# Pump_Agri.net
KiCad netlist of a schematic drawn in Altium Designer
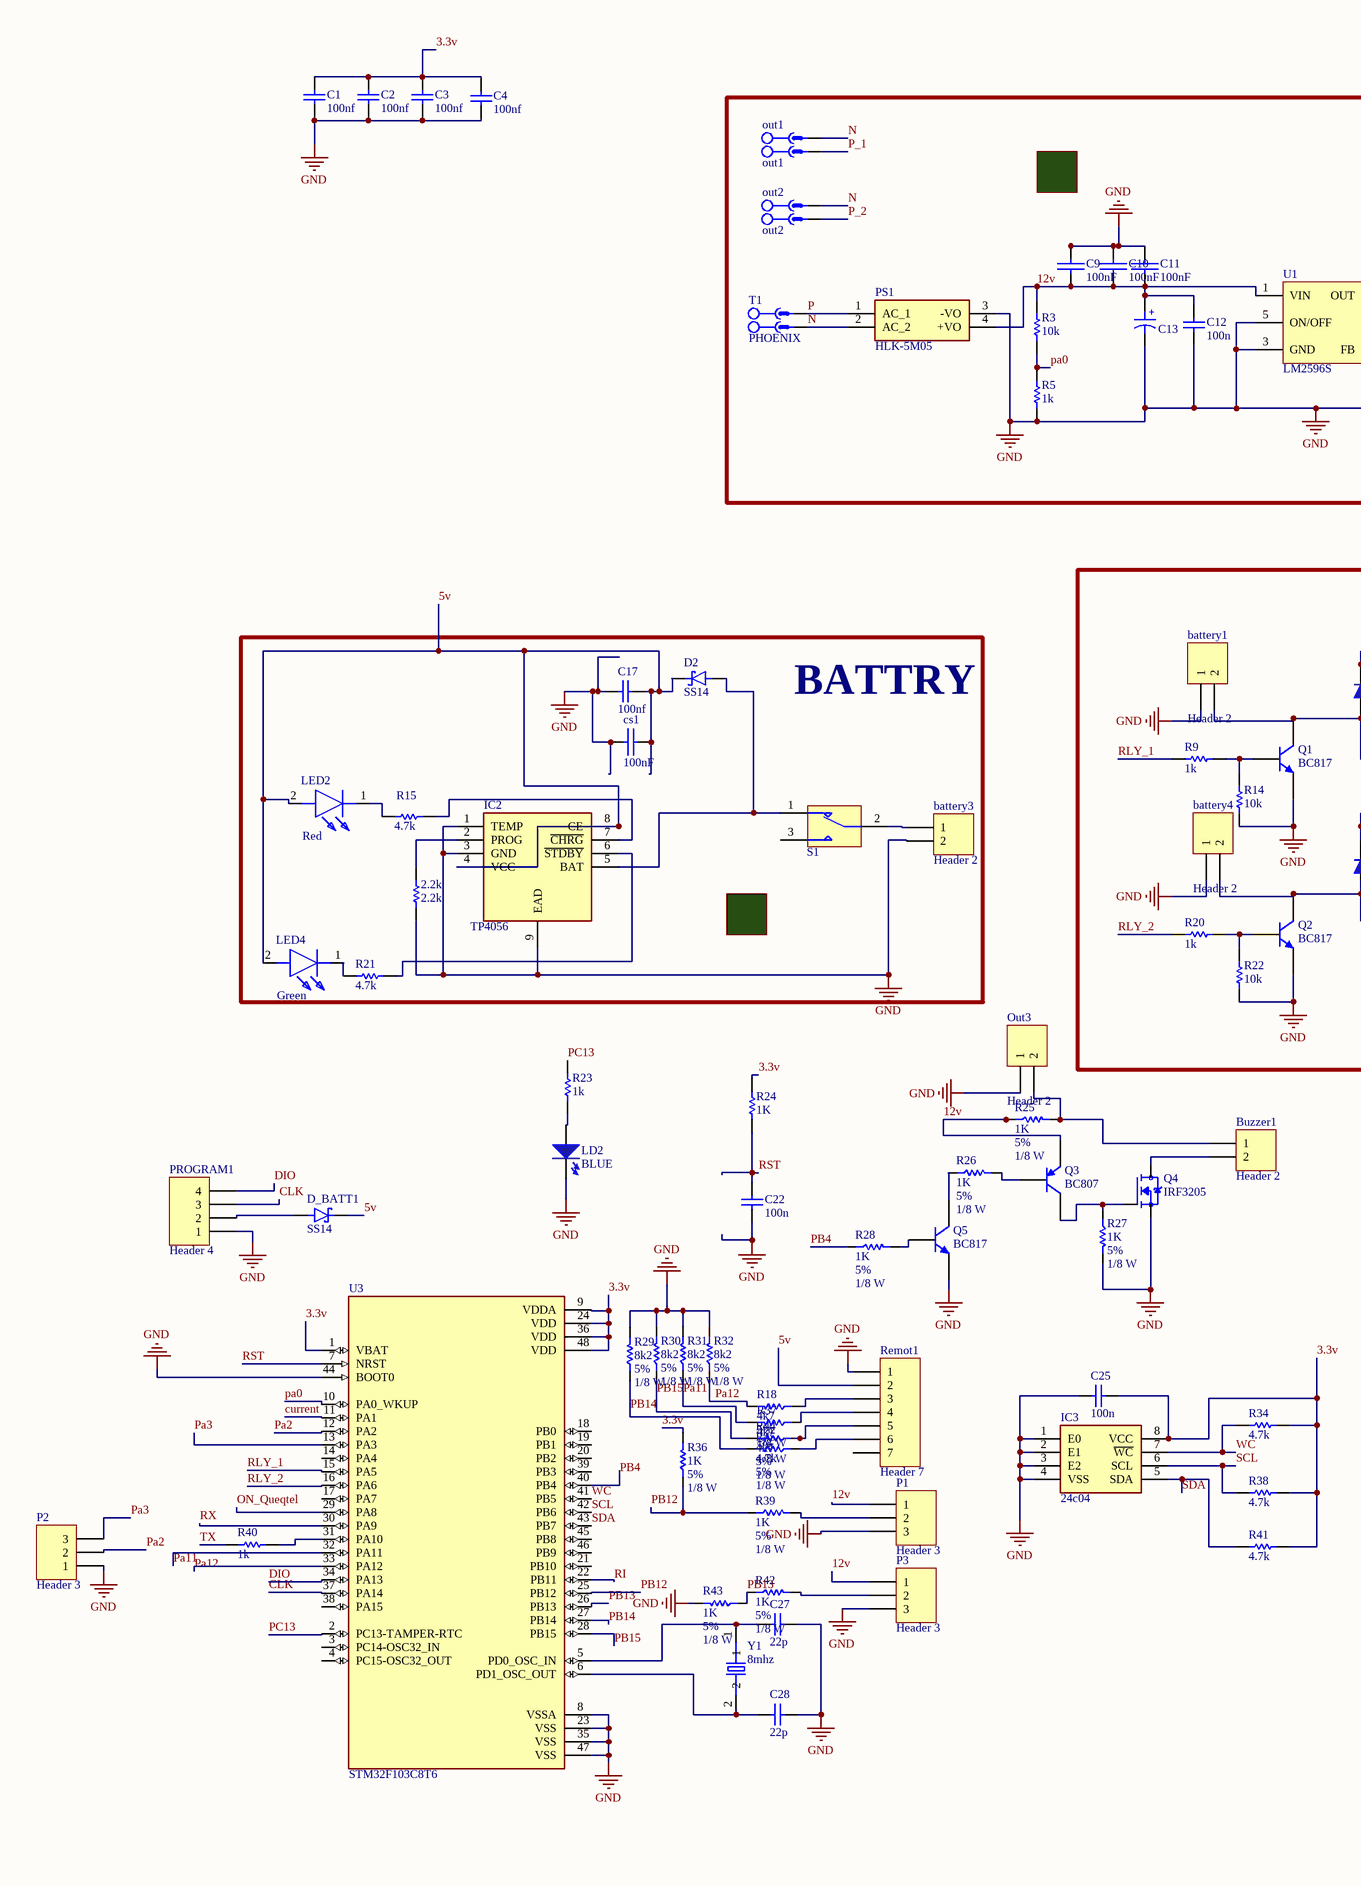
[diagram p0: Pump_Agri.SchDoc, left]
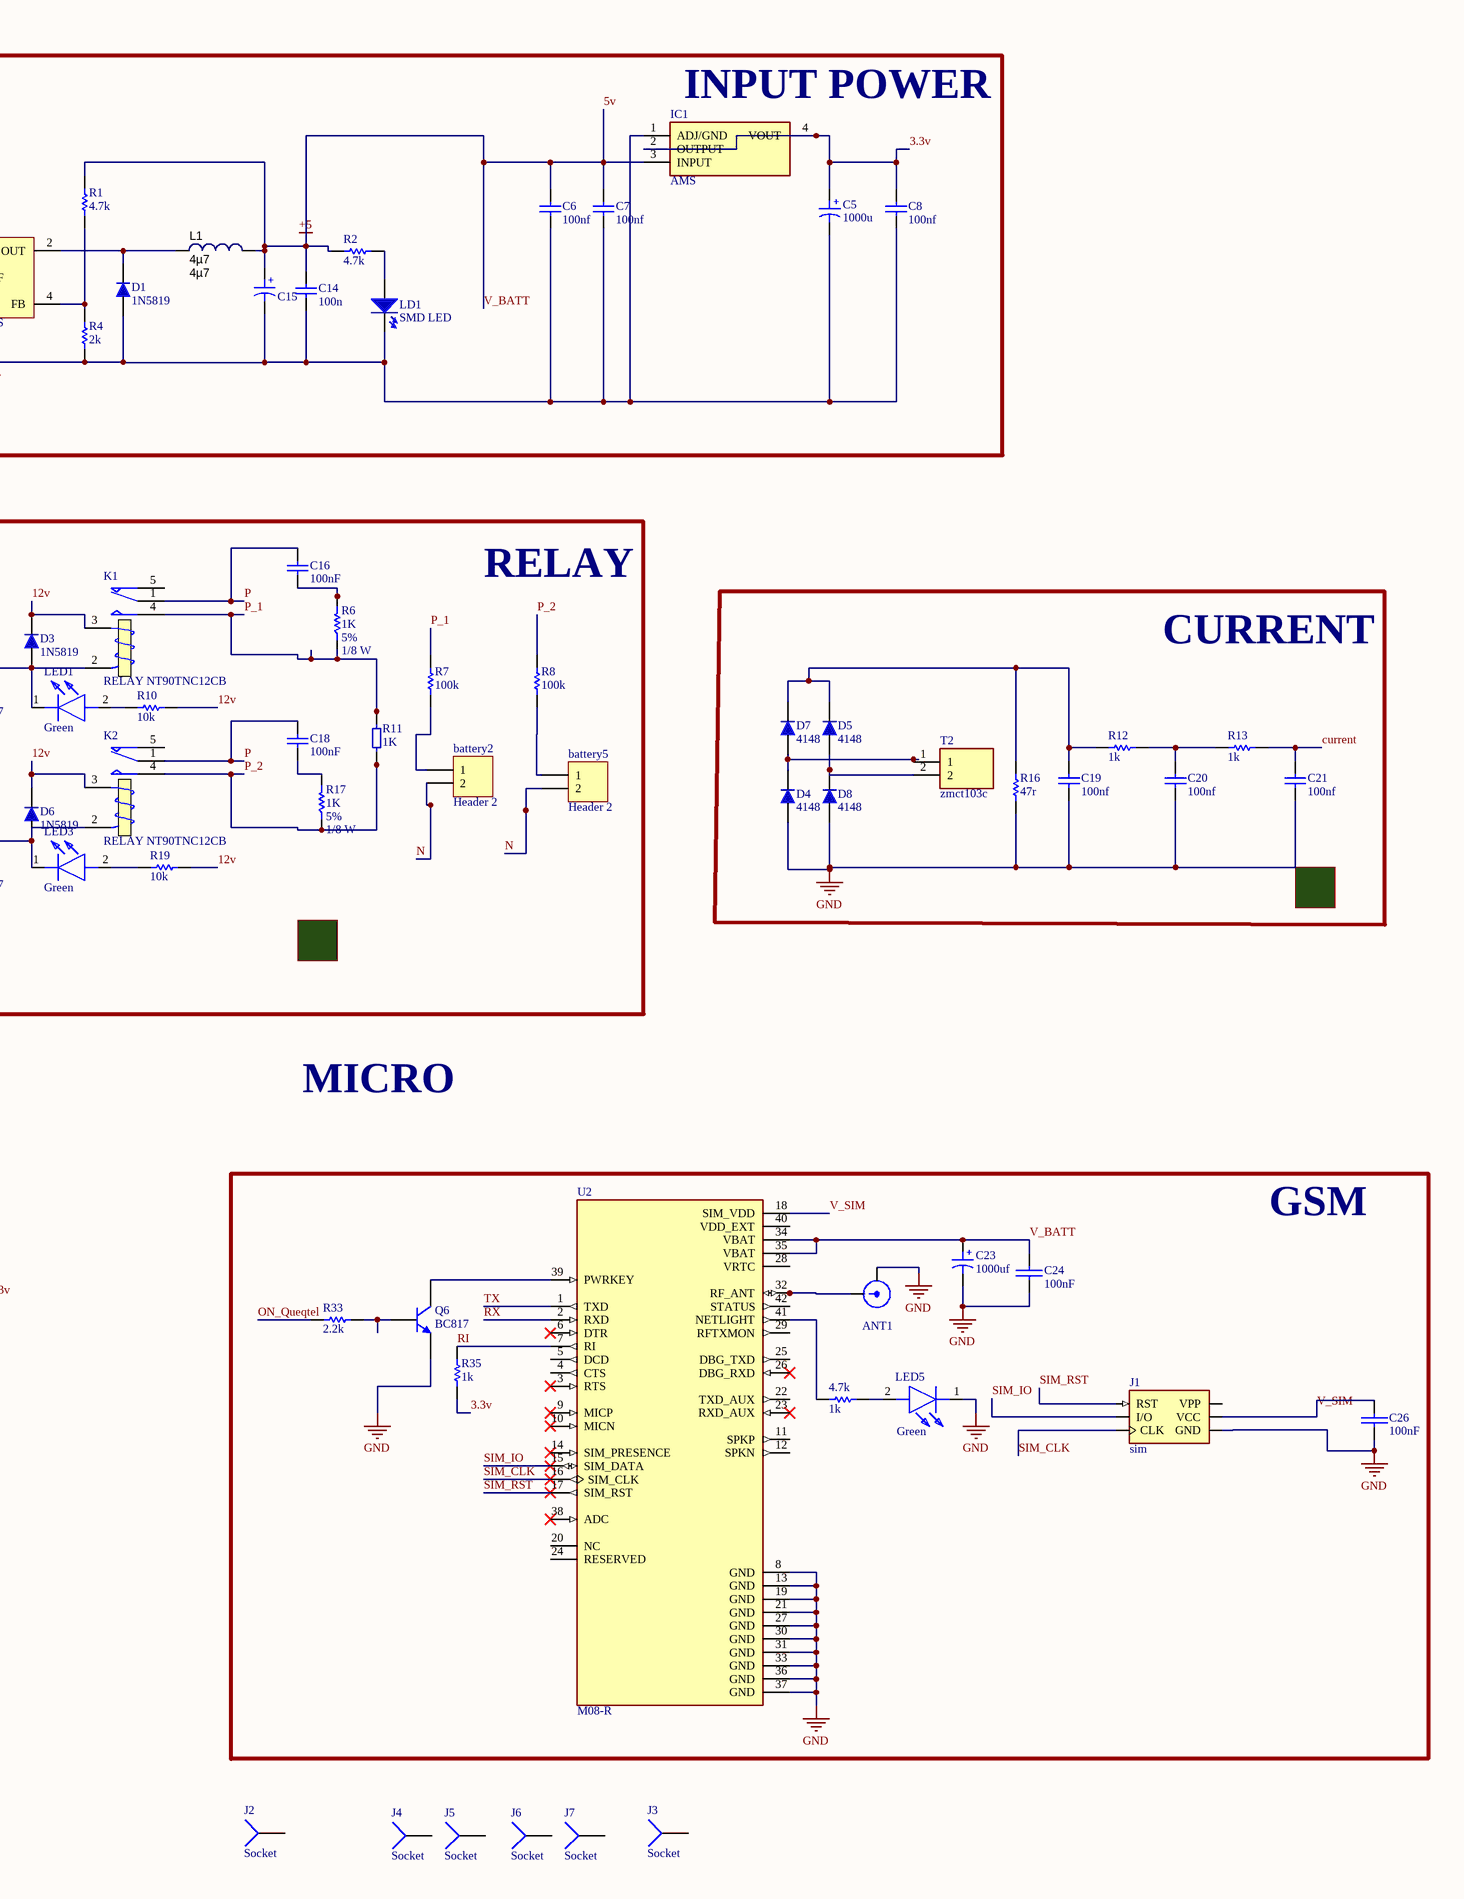
[diagram p1: Pump_Agri.SchDoc, right]

(export (version "E")
  (design (tool "Eeschema 10.0.6"))
  (components
    (comp (ref "2.2k")
      (value "2.2k")
      (footprint "RESC3413X04N")
      (description "RES 0805")
      (fields (field (name "DESIGNER") "Abbas Basereh"))
      (libsource (lib "2017AbbasBasereh9365731239 -ver1") (part "RES 0805 0.125W"))
    )
    (comp (ref "4.7k")
      (value "1k")
      (footprint "RESC3413X04N")
      (description "RES 0805")
      (fields (field (name "DESIGNER") "Abbas Basereh"))
      (libsource (lib "2017AbbasBasereh9365731239 -ver1") (part "RES 0805 0.125W"))
    )
    (comp (ref "ANT1")
      (value "ANT U.FL")
      (footprint "U.FL SMD")
      (description "Antenna")
      (libsource (lib "Altium") (part "ANT U.FL"))
    )
    (comp (ref "battery1")
      (value "Header 2")
      (footprint "HDR1X2")
      (description "Header, 2-Pin")
      (fields (field (name "PUBLISHER") "Altium Limited"))
      (libsource (lib "Miscellaneous Connectors") (part "Header 2"))
    )
    (comp (ref "battery2")
      (value "Header 2")
      (footprint "HDR1X2")
      (description "Header, 2-Pin")
      (fields (field (name "PUBLISHER") "Altium Limited"))
      (libsource (lib "") (part "Header 2_1"))
    )
    (comp (ref "battery3")
      (value "Header 2")
      (footprint "HDR1X2")
      (description "Header, 2-Pin")
      (fields (field (name "PUBLISHER") "Altium Limited"))
      (libsource (lib "") (part "Header 2_1"))
    )
    (comp (ref "battery4")
      (value "Header 2")
      (footprint "HDR1X2")
      (description "Header, 2-Pin")
      (fields (field (name "PUBLISHER") "Altium Limited"))
      (libsource (lib "Miscellaneous Connectors") (part "Header 2"))
    )
    (comp (ref "battery5")
      (value "Header 2")
      (footprint "HDR1X2")
      (description "Header, 2-Pin")
      (fields (field (name "PUBLISHER") "Altium Limited"))
      (libsource (lib "") (part "Header 2_1"))
    )
    (comp (ref "Buzzer1")
      (value "Header 2")
      (footprint "HDR1X2")
      (description "Header, 2-Pin")
      (fields (field (name "PUBLISHER") "Altium Limited"))
      (libsource (lib "") (part "Header 2_1"))
    )
    (comp (ref "C1")
      (value "100nf")
      (footprint "CAPC3413X12N")
      (description "CAP 0805")
      (fields (field (name "DESIGNER") "Abbas Basereh"))
      (libsource (lib "2017AbbasBasereh9365731239 -ver1") (part "CAP SMD 0805"))
    )
    (comp (ref "C2")
      (value "100nf")
      (footprint "CAPC3413X12N")
      (description "CAP 0805")
      (fields (field (name "DESIGNER") "Abbas Basereh"))
      (libsource (lib "2017AbbasBasereh9365731239 -ver1") (part "CAP SMD 0805"))
    )
    (comp (ref "C3")
      (value "100nf")
      (footprint "CAPC3413X12N")
      (description "CAP 0805")
      (fields (field (name "DESIGNER") "Abbas Basereh"))
      (libsource (lib "2017AbbasBasereh9365731239 -ver1") (part "CAP SMD 0805"))
    )
    (comp (ref "C4")
      (value "100nf")
      (footprint "CAPC3413X12N")
      (description "CAP 0805")
      (fields (field (name "DESIGNER") "Abbas Basereh"))
      (libsource (lib "2017AbbasBasereh9365731239 -ver1") (part "CAP SMD 0805"))
    )
    (comp (ref "C5")
      (value "1000u")
      (footprint "Cap electrolitic radial 8x12-3.5")
      (description "Cap electrolitic radial")
      (fields (field (name "DESIGNER") "Abbas Basereh"))
      (libsource (lib "Altium") (part "Cap ELECTROLITIC TOTAL SIZE"))
    )
    (comp (ref "C6")
      (value "100nf")
      (footprint "CAPC3413X12N")
      (description "CAP 0805")
      (fields (field (name "DESIGNER") "Abbas Basereh"))
      (libsource (lib "2017AbbasBasereh9365731239 -ver1") (part "CAP SMD 0805"))
    )
    (comp (ref "C7")
      (value "100nf")
      (footprint "CAPC3413X12N")
      (description "CAP 0805")
      (fields (field (name "DESIGNER") "Abbas Basereh"))
      (libsource (lib "2017AbbasBasereh9365731239 -ver1") (part "CAP SMD 0805"))
    )
    (comp (ref "C8")
      (value "100nf")
      (footprint "CAPC3413X12N")
      (description "CAP 0805")
      (fields (field (name "DESIGNER") "Abbas Basereh"))
      (libsource (lib "2017AbbasBasereh9365731239 -ver1") (part "CAP SMD 0805"))
    )
    (comp (ref "C9")
      (value "100nF")
      (footprint "SMD_CAP_1206")
      (description "Bipolar Capacitor")
      (fields (field (name "VOLTAGE") "100V") (field (name "DESIGNER") "Saeid Jorablo"))
      (libsource (lib "My_Library") (part "Cap-Bipolar"))
    )
    (comp (ref "C10")
      (value "100nF")
      (footprint "SMD_CAP_1206")
      (description "Bipolar Capacitor")
      (fields (field (name "VOLTAGE") "100V") (field (name "DESIGNER") "Saeid Jorablo"))
      (libsource (lib "My_Library") (part "Cap-Bipolar"))
    )
    (comp (ref "C11")
      (value "100nF")
      (footprint "SMD_CAP_1206")
      (description "Bipolar Capacitor")
      (fields (field (name "VOLTAGE") "100V") (field (name "DESIGNER") "Saeid Jorablo"))
      (libsource (lib "My_Library") (part "Cap-Bipolar"))
    )
    (comp (ref "C12")
      (value "100n")
      (footprint "CAPC3413X12N")
      (description "CAP 0805")
      (fields (field (name "DESIGNER") "Abbas Basereh"))
      (libsource (lib "Altium") (part "CAP SMD 0805"))
    )
    (comp (ref "C13")
      (value "1000u")
      (footprint "Cap electrolitic radial 10x20-5")
      (description "Cap electrolitic radial")
      (fields (field (name "DESIGNER") "Abbas Basereh"))
      (libsource (lib "Altium") (part "Cap electrolitic radial 10x21"))
    )
    (comp (ref "C14")
      (value "100n")
      (footprint "CAPC3413X12N")
      (description "CAP 0805")
      (fields (field (name "DESIGNER") "Abbas Basereh"))
      (libsource (lib "Altium") (part "CAP SMD 0805"))
    )
    (comp (ref "C15")
      (value "100u")
      (footprint "Cap electrolitic radial 10x20-5")
      (description "Cap electrolitic radial")
      (fields (field (name "DESIGNER") "Abbas Basereh"))
      (libsource (lib "Altium") (part "Cap electrolitic radial 10x21"))
    )
    (comp (ref "C16")
      (value "100nF")
      (footprint "Cap-10nF-630V")
      (description "CAP Ceramic Total")
      (fields (field (name "DESIGNER") "Ali Hafizi"))
      (libsource (lib "Altium") (part "CAP CERAMIC TOTAL SIZE"))
    )
    (comp (ref "C17")
      (value "100nf")
      (footprint "CAPC3413X12N")
      (description "CAP 0805")
      (fields (field (name "DESIGNER") "Abbas Basereh"))
      (libsource (lib "2017AbbasBasereh9365731239 -ver1") (part "CAP SMD 0805"))
    )
    (comp (ref "C18")
      (value "100nF")
      (footprint "Cap-10nF-630V")
      (description "CAP Ceramic Total")
      (fields (field (name "DESIGNER") "Ali Hafizi"))
      (libsource (lib "Altium") (part "CAP CERAMIC TOTAL SIZE"))
    )
    (comp (ref "C19")
      (value "100nf")
      (footprint "CAPC3413X12N")
      (description "CAP 0805")
      (fields (field (name "DESIGNER") "Abbas Basereh"))
      (libsource (lib "2017AbbasBasereh9365731239 -ver1") (part "CAP SMD 0805"))
    )
    (comp (ref "C20")
      (value "100nf")
      (footprint "CAPC3413X12N")
      (description "CAP 0805")
      (fields (field (name "DESIGNER") "Abbas Basereh"))
      (libsource (lib "2017AbbasBasereh9365731239 -ver1") (part "CAP SMD 0805"))
    )
    (comp (ref "C21")
      (value "100nf")
      (footprint "CAPC3413X12N")
      (description "CAP 0805")
      (fields (field (name "DESIGNER") "Abbas Basereh"))
      (libsource (lib "2017AbbasBasereh9365731239 -ver1") (part "CAP SMD 0805"))
    )
    (comp (ref "C22")
      (value "100n")
      (footprint "CAPC3413X12N")
      (description "CAP 0805")
      (fields (field (name "DESIGNER") "Abbas Basereh"))
      (libsource (lib "Altium") (part "CAP SMD 0805"))
    )
    (comp (ref "C23")
      (value "1000uf")
      (footprint "Cap electrolitic radial 8x12-3.5")
      (description "Cap electrolitic radial")
      (fields (field (name "DESIGNER") "Abbas Basereh"))
      (libsource (lib "Altium") (part "Cap ELECTROLITIC TOTAL SIZE"))
    )
    (comp (ref "C24")
      (value "100nF")
      (footprint "CAP0805")
      (description "Bipolar Capacitor")
      (fields
        (field (name "VOLTAGE") "100V")
        (field (name "Comment") "100N")
        (field (name "DESIGNER") "Saeid Jorablo")
      )
      (libsource (lib "My_Library") (part "Cap-Bipolar"))
    )
    (comp (ref "C25")
      (value "100n")
      (footprint "CAPC3413X12N")
      (description "CAP 0805")
      (fields (field (name "DESIGNER") "Abbas Basereh"))
      (libsource (lib "Altium") (part "CAP SMD 0805"))
    )
    (comp (ref "C26")
      (value "100nF")
      (footprint "CAP0805")
      (description "Bipolar Capacitor")
      (fields
        (field (name "VOLTAGE") "100V")
        (field (name "Comment") "100N")
        (field (name "DESIGNER") "Saeid Jorablo")
      )
      (libsource (lib "My_Library") (part "Cap-Bipolar"))
    )
    (comp (ref "C27")
      (value "22p")
      (footprint "CAPC3413X12N")
      (description "CAP 0805")
      (fields (field (name "DESIGNER") "Abbas Basereh"))
      (libsource (lib "2017AbbasBasereh9365731239 -ver1") (part "CAP SMD 0805"))
    )
    (comp (ref "C28")
      (value "22p")
      (footprint "CAPC3413X12N")
      (description "CAP 0805")
      (fields (field (name "DESIGNER") "Abbas Basereh"))
      (libsource (lib "2017AbbasBasereh9365731239 -ver1") (part "CAP SMD 0805"))
    )
    (comp (ref "cs1")
      (value "100nF")
      (footprint "SMD_CAP_1206")
      (description "Bipolar Capacitor")
      (fields (field (name "VOLTAGE") "100V") (field (name "DESIGNER") "Saeid Jorablo"))
      (libsource (lib "My_Library") (part "Cap-Bipolar"))
    )
    (comp (ref "D1")
      (value "1N5819")
      (footprint "DO-214AA(SMA)")
      (libsource (lib "ZetaBoard Altium Lib 14000319") (part "1N5819(SS14)"))
    )
    (comp (ref "D2")
      (value "SS14")
      (footprint "DIOM4325X250N")
      (description "1A, 40V, Schottky Rectifier")
      (fields (field (name "MF") "Taiwan Semiconductor"))
      (libsource (lib "SS14") (part "SS14"))
    )
    (comp (ref "D3")
      (value "1N5819")
      (footprint "DO-214AA(SMA)")
      (libsource (lib "ZetaBoard Altium Lib 14000319") (part "1N5819(SS14)"))
    )
    (comp (ref "D4")
      (value "4148")
      (footprint "SOD80, LL-34")
      (description "DIODE GEN PURP 75V 200MA DO213AA")
      (fields (field (name "PUBLISHER") "Abbas Basereh"))
      (libsource (lib "2017AbbasBasereh9365731239 -ver1") (part "1N4148UR-1"))
    )
    (comp (ref "D5")
      (value "4148")
      (footprint "SOD80, LL-34")
      (description "DIODE GEN PURP 75V 200MA DO213AA")
      (fields (field (name "PUBLISHER") "Abbas Basereh"))
      (libsource (lib "2017AbbasBasereh9365731239 -ver1") (part "1N4148UR-1"))
    )
    (comp (ref "D6")
      (value "1N5819")
      (footprint "DO-214AA(SMA)")
      (libsource (lib "ZetaBoard Altium Lib 14000319") (part "1N5819(SS14)"))
    )
    (comp (ref "D7")
      (value "4148")
      (footprint "SOD80, LL-34")
      (description "DIODE GEN PURP 75V 200MA DO213AA")
      (fields (field (name "PUBLISHER") "Abbas Basereh"))
      (libsource (lib "2017AbbasBasereh9365731239 -ver1") (part "1N4148UR-1"))
    )
    (comp (ref "D8")
      (value "4148")
      (footprint "SOD80, LL-34")
      (description "DIODE GEN PURP 75V 200MA DO213AA")
      (fields (field (name "PUBLISHER") "Abbas Basereh"))
      (libsource (lib "2017AbbasBasereh9365731239 -ver1") (part "1N4148UR-1"))
    )
    (comp (ref "D_BATT1") (value "SS14") (footprint "DIOM4325X250N") (libsource (lib "SS14") (part "SS14")))
    (comp (ref "IC1")
      (value "AMS")
      (footprint "SamacSys:SOT230P700X180-4N")
      (description "Integrated Circuit")
      (fields
        (field (name "MANUFACTURER_PART_NUMBER") "LM1117IMPX-ADJ/NOPB")
        (field (name "MOUSER PART NUMBER") "926-M1117IMPXADJNOPB")
      )
      (libsource (lib "*") (part "LM1117IMPX-ADJ_NOPB"))
    )
    (comp (ref "IC2")
      (value "TP4056")
      (footprint "SamacSys:SOIC127P600X175-9N")
      (description "Integrated Circuit")
      (fields (field (name "MANUFACTURER_PART_NUMBER") "TP4056X"))
      (libsource (lib "*") (part "TP4056X"))
    )
    (comp (ref "IC3")
      (value "24c04")
      (footprint "SamacSys:SOIC127P600X175-8N")
      (description "Integrated Circuit")
      (fields
        (field (name "MANUFACTURER_PART_NUMBER") "M24C02-RMN6P")
        (field (name "MOUSER PART NUMBER") "511-M24C02-RMN6P")
      )
      (libsource (lib "*") (part "M24C02-RMN6P"))
    )
    (comp (ref "J1")
      (value "sim")
      (footprint "GCT_SIM5060-6-0-26-01-X_REVC")
      (description "SIM Card Connector, Hinged Type 6 Pin, SMT, 2.6mm Profile, Optional Locating Post")
      (fields (field (name "MP") "SIM5060-6-0-26-01-X") (field (name "MF") "Global Connector Technology"))
      (libsource (lib "SIM5060-6-0-26-01-X_REVC") (part "SIM5060-6-0-26-01-X_REVC"))
    )
    (comp (ref "J2")
      (value "Socket")
      (footprint "Test Point")
      (fields (field (name "PUBLISHER") "Altium Limited"))
      (libsource (lib "Miscellaneous Connectors") (part "Socket"))
    )
    (comp (ref "J3")
      (value "Socket")
      (footprint "Test Point")
      (fields (field (name "PUBLISHER") "Altium Limited"))
      (libsource (lib "Miscellaneous Connectors") (part "Socket"))
    )
    (comp (ref "J4")
      (value "Socket")
      (footprint "Test Point")
      (fields (field (name "PUBLISHER") "Altium Limited"))
      (libsource (lib "Miscellaneous Connectors") (part "Socket"))
    )
    (comp (ref "J5")
      (value "Socket")
      (footprint "Test Point")
      (fields (field (name "PUBLISHER") "Altium Limited"))
      (libsource (lib "Miscellaneous Connectors") (part "Socket"))
    )
    (comp (ref "J6")
      (value "Socket")
      (footprint "Test Point")
      (fields (field (name "PUBLISHER") "Altium Limited"))
      (libsource (lib "Miscellaneous Connectors") (part "Socket"))
    )
    (comp (ref "J7")
      (value "Socket")
      (footprint "Test Point")
      (fields (field (name "PUBLISHER") "Altium Limited"))
      (libsource (lib "Miscellaneous Connectors") (part "Socket"))
    )
    (comp (ref "K1")
      (value "RELAY NT90TNC12CB")
      (footprint "RELAY NT90TNC12CB")
      (description "Relay_SPDT POWER NEEDLE")
      (fields (field (name "DESIGNER") "Abbas Basereh"))
      (libsource (lib "2017AbbasBasereh9365731239 -ver1") (part "RELAY NT90TNC12CB"))
    )
    (comp (ref "K2")
      (value "RELAY NT90TNC12CB")
      (footprint "RELAY NT90TNC12CB")
      (description "Relay_SPDT POWER NEEDLE")
      (fields (field (name "DESIGNER") "Abbas Basereh"))
      (libsource (lib "2017AbbasBasereh9365731239 -ver1") (part "RELAY NT90TNC12CB"))
    )
    (comp (ref "L1")
      (value "4µ7")
      (footprint "Inductor SMD 3x3.2mm")
      (description "Inductor 4.7µH SMD 3x3.2mm")
      (fields (field (name "TOLERANCE") "±20%") (field (name "ALTIUM_VALUE") "4µ7"))
      (libsource (lib "2017AbbasBasereh9365731239 -ver1") (part "Inductor 4.7µH SMD 3x3.2mm"))
    )
    (comp (ref "LD1")
      (value "SMD LED")
      (footprint "LED_0805 G")
      (libsource (lib "ZetaBoard Altium Lib 14000319") (part "LED SMD"))
    )
    (comp (ref "LD2")
      (value "BLUE")
      (footprint "LED_0805 G")
      (libsource (lib "ZetaBoard Altium Lib 14000319") (part "LED SMD"))
    )
    (comp (ref "LED1")
      (value "Green")
      (footprint "SamacSys:LEDC2012X80N")
      (description "LED")
      (fields
        (field (name "MANUFACTURER_PART_NUMBER") "150080BS75000")
        (field (name "MOUSER PART NUMBER") "710-150080BS75000")
      )
      (libsource (lib "*") (part "150080BS75000"))
    )
    (comp (ref "LED2")
      (value "Red")
      (footprint "SamacSys:LEDC2012X80N")
      (description "LED")
      (fields
        (field (name "MANUFACTURER_PART_NUMBER") "150080BS75000")
        (field (name "MOUSER PART NUMBER") "710-150080BS75000")
      )
      (libsource (lib "*") (part "150080BS75000"))
    )
    (comp (ref "LED3")
      (value "Green")
      (footprint "SamacSys:LEDC2012X80N")
      (description "LED")
      (fields
        (field (name "MANUFACTURER_PART_NUMBER") "150080BS75000")
        (field (name "MOUSER PART NUMBER") "710-150080BS75000")
      )
      (libsource (lib "*") (part "150080BS75000"))
    )
    (comp (ref "LED4")
      (value "Green")
      (footprint "SamacSys:LEDC2012X80N")
      (description "LED")
      (fields
        (field (name "MANUFACTURER_PART_NUMBER") "150080BS75000")
        (field (name "MOUSER PART NUMBER") "710-150080BS75000")
      )
      (libsource (lib "*") (part "150080BS75000"))
    )
    (comp (ref "LED5")
      (value "Green")
      (footprint "SamacSys:LEDC2012X80N")
      (description "LED")
      (fields
        (field (name "MANUFACTURER_PART_NUMBER") "150080BS75000")
        (field (name "MOUSER PART NUMBER") "710-150080BS75000")
      )
      (libsource (lib "*") (part "150080BS75000"))
    )
    (comp (ref "out1")
      (value "out1")
      (footprint "MSTBV 2,5/2-G-5")
      (description "2 Pitch: 5 mm Color: green Contact surface: Tin Assembly")
      (fields
        (field (name "MANUFACTURER") "PHOENIX CONTACT")
        (field (name "VOLTAGE") "320 V")
        (field (name "DESIGNER") "ABBAS BASEREH")
      )
      (libsource (lib "Altium") (part "CON_Phoenix_MSTBV_02"))
    )
    (comp (ref "out2")
      (value "out2")
      (footprint "MSTBV 2,5/2-G-5")
      (description "2 Pitch: 5 mm Color: green Contact surface: Tin Assembly")
      (fields
        (field (name "MANUFACTURER") "PHOENIX CONTACT")
        (field (name "VOLTAGE") "320 V")
        (field (name "DESIGNER") "ABBAS BASEREH")
      )
      (libsource (lib "Altium") (part "CON_Phoenix_MSTBV_02"))
    )
    (comp (ref "Out3")
      (value "Header 2")
      (footprint "HDR1X2")
      (description "Header, 2-Pin")
      (fields (field (name "PUBLISHER") "Altium Limited"))
      (libsource (lib "Miscellaneous Connectors") (part "Header 2"))
    )
    (comp (ref "P1")
      (value "Header 3")
      (footprint "HDR1X3")
      (description "Header, 3-Pin")
      (fields (field (name "PUBLISHER") "Altium Limited"))
      (libsource (lib "") (part "Header 3_1"))
    )
    (comp (ref "P2")
      (value "Header 3")
      (footprint "HDR1X3")
      (description "Header, 3-Pin")
      (fields (field (name "PUBLISHER") "Altium Limited"))
      (libsource (lib "Altium") (part "Header 3"))
    )
    (comp (ref "P3")
      (value "Header 3")
      (footprint "HDR1X3")
      (description "Header, 3-Pin")
      (fields (field (name "PUBLISHER") "Altium Limited"))
      (libsource (lib "") (part "Header 3_1"))
    )
    (comp (ref "PROGRAM1")
      (value "Header 4")
      (footprint "HDR1X4")
      (description "Header, 4-Pin")
      (fields (field (name "PUBLISHER") "Altium Limited"))
      (libsource (lib "Miscellaneous Connectors") (part "Header 4"))
    )
    (comp (ref "PS1")
      (value "HLK-5M05")
      (footprint "SamacSys:HLK5M05")
      (description "Power Supply")
      (libsource (lib "*") (part "HLK-5M05"))
    )
    (comp (ref "Q1")
      (value "BC817")
      (footprint "SOT-23")
      (libsource (lib "ZetaBoard Altium Lib 14000319") (part "BC817"))
    )
    (comp (ref "Q2")
      (value "BC817")
      (footprint "SOT-23")
      (libsource (lib "ZetaBoard Altium Lib 14000319") (part "BC817"))
    )
    (comp (ref "Q3")
      (value "BC807")
      (footprint "SOT23_BEC_N")
      (description "PNP Bipolar Transistor")
      (fields (field (name "PUBLISHER") "Altium Limited"))
      (libsource (lib "My_Library") (part "PNP"))
    )
    (comp (ref "Q4")
      (value "IRF3205")
      (footprint "TO254P1041X444X2933-3")
      (description "N-Channel 55V 110A (Tc) 200W (Tc) Through Hole TO-220AB")
      (fields (field (name "MF") "Infineon Technologies"))
      (libsource (lib "IRF3205") (part "IRF3205"))
    )
    (comp (ref "Q5")
      (value "BC817")
      (footprint "SOT23_BEC_N")
      (description "NPN Bipolar Transistor")
      (fields (field (name "PUBLISHER") "Altium Limited"))
      (libsource (lib "My_Library") (part "NPN"))
    )
    (comp (ref "Q6")
      (value "BC817")
      (footprint "SOT-23")
      (libsource (lib "ZetaBoard Altium Lib 14000319") (part "BC817"))
    )
    (comp (ref "R1")
      (value "4.7k")
      (footprint "RESC3413X04N")
      (description "RES 0805")
      (fields (field (name "DESIGNER") "Abbas Basereh"))
      (libsource (lib "2017AbbasBasereh9365731239 -ver1") (part "RES 0805 0.125W"))
    )
    (comp (ref "R2")
      (value "4.7k")
      (footprint "RESC3413X04N")
      (description "RES 0805")
      (fields (field (name "DESIGNER") "Abbas Basereh"))
      (libsource (lib "Altium") (part "RES 0805 0.125W"))
    )
    (comp (ref "R3")
      (value "10k")
      (footprint "RESC3413X04N")
      (description "RES 0805")
      (fields (field (name "DESIGNER") "Abbas Basereh"))
      (libsource (lib "2017AbbasBasereh9365731239 -ver1") (part "RES 0805 0.125W"))
    )
    (comp (ref "R4")
      (value "2k")
      (footprint "RESC3413X04N")
      (description "RES 0805")
      (fields (field (name "DESIGNER") "Abbas Basereh"))
      (libsource (lib "2017AbbasBasereh9365731239 -ver1") (part "RES 0805 0.125W"))
    )
    (comp (ref "R5")
      (value "1k")
      (footprint "RESC3413X04N")
      (description "RES 0805")
      (fields (field (name "DESIGNER") "Abbas Basereh"))
      (libsource (lib "2017AbbasBasereh9365731239 -ver1") (part "RES 0805 0.125W"))
    )
    (comp (ref "R6")
      (value "1K")
      (footprint "Res-(1/4)-Stand")
      (description "Resistor")
      (fields (field (name "TOLERANCE") "5%") (field (name "POWER") "1/8 W"))
      (libsource (lib "My_Library") (part "Resistor"))
    )
    (comp (ref "R7")
      (value "100k")
      (footprint "RESC3413X04N")
      (description "RES 0805")
      (fields (field (name "DESIGNER") "Abbas Basereh"))
      (libsource (lib "2017AbbasBasereh9365731239 -ver1") (part "RES 0805 0.125W"))
    )
    (comp (ref "R8")
      (value "100k")
      (footprint "RESC3413X04N")
      (description "RES 0805")
      (fields (field (name "DESIGNER") "Abbas Basereh"))
      (libsource (lib "2017AbbasBasereh9365731239 -ver1") (part "RES 0805 0.125W"))
    )
    (comp (ref "R9")
      (value "1k")
      (footprint "RESC3413X04N")
      (description "RES 0805")
      (fields (field (name "DESIGNER") "Abbas Basereh"))
      (libsource (lib "2017AbbasBasereh9365731239 -ver1") (part "RES 0805 0.125W"))
    )
    (comp (ref "R10")
      (value "10k")
      (footprint "RESC3413X04N")
      (description "RES 0805")
      (fields (field (name "DESIGNER") "Abbas Basereh"))
      (libsource (lib "2017AbbasBasereh9365731239 -ver1") (part "RES 0805 0.125W"))
    )
    (comp (ref "R11")
      (value "Resistor SMD")
      (footprint "2512 Resistor")
      (fields (field (name "ALTIUM_UNNAMED_1") "1K"))
      (libsource (lib "ZetaBoard Altium Lib 14000319") (part "Resistor SMD"))
    )
    (comp (ref "R12")
      (value "1k")
      (footprint "RESC3413X04N")
      (description "RES 0805")
      (fields (field (name "DESIGNER") "Abbas Basereh"))
      (libsource (lib "2017AbbasBasereh9365731239 -ver1") (part "RES 0805 0.125W"))
    )
    (comp (ref "R13")
      (value "1k")
      (footprint "RESC3413X04N")
      (description "RES 0805")
      (fields (field (name "DESIGNER") "Abbas Basereh"))
      (libsource (lib "2017AbbasBasereh9365731239 -ver1") (part "RES 0805 0.125W"))
    )
    (comp (ref "R14")
      (value "10k")
      (footprint "RESC3413X04N")
      (description "RES 0805")
      (fields (field (name "DESIGNER") "Abbas Basereh"))
      (libsource (lib "2017AbbasBasereh9365731239 -ver1") (part "RES 0805 0.125W"))
    )
    (comp (ref "R15")
      (value "4.7k")
      (footprint "RESC3413X04N")
      (description "RES 0805")
      (fields (field (name "DESIGNER") "Abbas Basereh"))
      (libsource (lib "2017AbbasBasereh9365731239 -ver1") (part "RES 0805 0.125W"))
    )
    (comp (ref "R16")
      (value "47r")
      (footprint "RESC3413X04N")
      (description "RES 0805")
      (fields (field (name "DESIGNER") "Abbas Basereh"))
      (libsource (lib "2017AbbasBasereh9365731239 -ver1") (part "RES 0805 0.125W"))
    )
    (comp (ref "R17")
      (value "1K")
      (footprint "Res-(1/4)-Stand")
      (description "Resistor")
      (fields (field (name "TOLERANCE") "5%") (field (name "POWER") "1/8 W"))
      (libsource (lib "My_Library") (part "Resistor"))
    )
    (comp (ref "R18")
      (value "4k7")
      (footprint "SMD_RES_1206")
      (description "Resistor")
      (fields (field (name "TOLERANCE") "5%") (field (name "POWER") "1/8 W"))
      (libsource (lib "My_Library") (part "Resistor"))
    )
    (comp (ref "R19")
      (value "10k")
      (footprint "RESC3413X04N")
      (description "RES 0805")
      (fields (field (name "DESIGNER") "Abbas Basereh"))
      (libsource (lib "2017AbbasBasereh9365731239 -ver1") (part "RES 0805 0.125W"))
    )
    (comp (ref "R20")
      (value "1k")
      (footprint "RESC3413X04N")
      (description "RES 0805")
      (fields (field (name "DESIGNER") "Abbas Basereh"))
      (libsource (lib "2017AbbasBasereh9365731239 -ver1") (part "RES 0805 0.125W"))
    )
    (comp (ref "R21")
      (value "4.7k")
      (footprint "RESC3413X04N")
      (description "RES 0805")
      (fields (field (name "DESIGNER") "Abbas Basereh"))
      (libsource (lib "2017AbbasBasereh9365731239 -ver1") (part "RES 0805 0.125W"))
    )
    (comp (ref "R22")
      (value "10k")
      (footprint "RESC3413X04N")
      (description "RES 0805")
      (fields (field (name "DESIGNER") "Abbas Basereh"))
      (libsource (lib "2017AbbasBasereh9365731239 -ver1") (part "RES 0805 0.125W"))
    )
    (comp (ref "R23")
      (value "1k")
      (footprint "RESC3413X04N")
      (description "RES 0805")
      (fields (field (name "DESIGNER") "Abbas Basereh"))
      (libsource (lib "Altium") (part "RES 0805 0.125W"))
    )
    (comp (ref "R24")
      (value "1K")
      (footprint "RESC3413X04N")
      (description "RES 0805")
      (fields (field (name "DESIGNER") "Abbas Basereh"))
      (libsource (lib "Altium") (part "RES 0805 0.125W"))
    )
    (comp (ref "R25")
      (value "1K")
      (footprint "RES 1206 (3216X08L)")
      (description "Resistor")
      (fields (field (name "TOLERANCE") "5%") (field (name "POWER") "1/8 W"))
      (libsource (lib "My_Library") (part "Resistor"))
    )
    (comp (ref "R26")
      (value "1K")
      (footprint "RES 1206 (3216X08L)")
      (description "Resistor")
      (fields (field (name "TOLERANCE") "5%") (field (name "POWER") "1/8 W") (field (name "Comment") "4.7k"))
      (libsource (lib "My_Library") (part "Resistor"))
    )
    (comp (ref "R27")
      (value "1K")
      (footprint "RES 1206 (3216X08L)")
      (description "Resistor")
      (fields (field (name "TOLERANCE") "5%") (field (name "POWER") "1/8 W") (field (name "Comment") "10k"))
      (libsource (lib "My_Library") (part "Resistor"))
    )
    (comp (ref "R28")
      (value "1K")
      (footprint "RES 1206 (3216X08L)")
      (description "Resistor")
      (fields (field (name "TOLERANCE") "5%") (field (name "POWER") "1/8 W") (field (name "Comment") "4.7k"))
      (libsource (lib "My_Library") (part "Resistor"))
    )
    (comp (ref "R29")
      (value "8k2")
      (footprint "SMD_RES_1206")
      (description "Resistor")
      (fields (field (name "TOLERANCE") "5%") (field (name "POWER") "1/8 W"))
      (libsource (lib "My_Library") (part "Resistor"))
    )
    (comp (ref "R30")
      (value "8k2")
      (footprint "SMD_RES_1206")
      (description "Resistor")
      (fields (field (name "TOLERANCE") "5%") (field (name "POWER") "1/8 W"))
      (libsource (lib "My_Library") (part "Resistor"))
    )
    (comp (ref "R31")
      (value "8k2")
      (footprint "SMD_RES_1206")
      (description "Resistor")
      (fields (field (name "TOLERANCE") "5%") (field (name "POWER") "1/8 W"))
      (libsource (lib "My_Library") (part "Resistor"))
    )
    (comp (ref "R32")
      (value "8k2")
      (footprint "SMD_RES_1206")
      (description "Resistor")
      (fields (field (name "TOLERANCE") "5%") (field (name "POWER") "1/8 W"))
      (libsource (lib "My_Library") (part "Resistor"))
    )
    (comp (ref "R33")
      (value "2.2k")
      (footprint "RESC3413X04N")
      (description "RES 0805")
      (fields (field (name "DESIGNER") "Abbas Basereh"))
      (libsource (lib "2017AbbasBasereh9365731239 -ver1") (part "RES 0805 0.125W"))
    )
    (comp (ref "R34")
      (value "4.7k")
      (footprint "RESC3413X04N")
      (description "RES 0805")
      (fields (field (name "DESIGNER") "Abbas Basereh"))
      (libsource (lib "2017AbbasBasereh9365731239 -ver1") (part "RES 0805 0.125W"))
    )
    (comp (ref "R35")
      (value "1k")
      (footprint "RESC3413X04N")
      (description "RES 0805")
      (fields (field (name "DESIGNER") "Abbas Basereh"))
      (libsource (lib "2017AbbasBasereh9365731239 -ver1") (part "RES 0805 0.125W"))
    )
    (comp (ref "R36")
      (value "1K")
      (footprint "SMD_RES_1206")
      (description "Resistor")
      (fields (field (name "TOLERANCE") "5%") (field (name "POWER") "1/8 W") (field (name "Comment") "4.7k"))
      (libsource (lib "My_Library") (part "Resistor"))
    )
    (comp (ref "R37")
      (value "4k7")
      (footprint "SMD_RES_1206")
      (description "Resistor")
      (fields (field (name "TOLERANCE") "5%") (field (name "POWER") "1/8 W"))
      (libsource (lib "My_Library") (part "Resistor"))
    )
    (comp (ref "R38")
      (value "4.7k")
      (footprint "RESC3413X04N")
      (description "RES 0805")
      (fields (field (name "DESIGNER") "Abbas Basereh"))
      (libsource (lib "2017AbbasBasereh9365731239 -ver1") (part "RES 0805 0.125W"))
    )
    (comp (ref "R39")
      (value "1K")
      (footprint "SMD_RES_1206")
      (description "Resistor")
      (fields (field (name "TOLERANCE") "5%") (field (name "POWER") "1/8 W") (field (name "Comment") "330r"))
      (libsource (lib "My_Library") (part "Resistor"))
    )
    (comp (ref "R40")
      (value "1k")
      (footprint "RESC3413X04N")
      (description "RES 0805")
      (fields (field (name "DESIGNER") "Abbas Basereh"))
      (libsource (lib "2017AbbasBasereh9365731239 -ver1") (part "RES 0805 0.125W"))
    )
    (comp (ref "R41")
      (value "4.7k")
      (footprint "RESC3413X04N")
      (description "RES 0805")
      (fields (field (name "DESIGNER") "Abbas Basereh"))
      (libsource (lib "2017AbbasBasereh9365731239 -ver1") (part "RES 0805 0.125W"))
    )
    (comp (ref "R42")
      (value "1K")
      (footprint "SMD_RES_1206")
      (description "Resistor")
      (fields (field (name "TOLERANCE") "5%") (field (name "POWER") "1/8 W") (field (name "Comment") "10k"))
      (libsource (lib "My_Library") (part "Resistor"))
    )
    (comp (ref "R43")
      (value "1K")
      (footprint "SMD_RES_1206")
      (description "Resistor")
      (fields (field (name "TOLERANCE") "5%") (field (name "POWER") "1/8 W") (field (name "Comment") "2.2k"))
      (libsource (lib "My_Library") (part "Resistor"))
    )
    (comp (ref "R44")
      (value "4k7")
      (footprint "SMD_RES_1206")
      (description "Resistor")
      (fields (field (name "TOLERANCE") "5%") (field (name "POWER") "1/8 W"))
      (libsource (lib "My_Library") (part "Resistor"))
    )
    (comp (ref "R45")
      (value "4.7k")
      (footprint "SMD_RES_1206")
      (description "Resistor")
      (fields (field (name "TOLERANCE") "5%") (field (name "POWER") "1/8 W"))
      (libsource (lib "My_Library") (part "Resistor"))
    )
    (comp (ref "Remot1")
      (value "Header 7")
      (footprint "HDR1X7")
      (description "Header, 7-Pin")
      (fields (field (name "PUBLISHER") "Altium Limited"))
      (libsource (lib "Miscellaneous Connectors") (part "Header 7"))
    )
    (comp (ref "S1")
      (value "Switch SPDT_Subminiator")
      (footprint "SPDT Subminiator")
      (description "Subminiator SPDT Switch")
      (libsource (lib "Altium") (part "Switch SPDT_Subminiator"))
    )
    (comp (ref "T1")
      (value "PHOENIX")
      (footprint "MSTBV 2,5/2-G-5")
      (description "2 Pitch: 5 mm Color: green Contact surface: Tin Assembly")
      (fields
        (field (name "MANUFACTURER") "PHOENIX CONTACT")
        (field (name "VOLTAGE") "320 V")
        (field (name "DESIGNER") "ABBAS BASEREH")
      )
      (libsource (lib "Altium") (part "CON_Phoenix_MSTBV_02"))
    )
    (comp (ref "T2")
      (value "zmct103c")
      (footprint "SamacSys:zmct103c")
      (description "Transformer")
      (libsource (lib "*") (part "zmct103c"))
    )
    (comp (ref "U1")
      (value "LM2596S")
      (footprint "TO - 263")
      (libsource (lib "ZetaBoard Altium Lib 14000319") (part "LM2596S"))
    )
    (comp (ref "U2") (value "M08-R") (footprint "XCVR_M08-R") (libsource (lib "M08-R") (part "M08-R")))
    (comp (ref "U3")
      (value "STM32F103C8T6")
      (footprint "QFP50P900X900X160-48N")
      (description "ARM® Cortex®-M3 STM32F1 Microcontroller IC 32-Bit 72MHz 64KB (64K x 8) FLASH 48-LQFP (7x7)")
      (fields (field (name "MF") "STMicroelectronics"))
      (libsource (lib "STM32F103C8T6") (part "STM32F103C8T6"))
    )
    (comp (ref "Y1")
      (value "8mhz")
      (footprint "XTAL1170X500X450")
      (fields (field (name "MF") "Fox Electronics") (field (name "MP") "FOXSDLF/120-20"))
      (libsource (lib "FOXSDLF_120-20") (part "FOXSDLF/120-20"))
    )
  )
  (nets
    (net (code "1") (name "+5") (class "Default")
      (node (ref "C14") (pin "2") (pinfunction "2_2") (pintype "passive"))
      (node (ref "C15") (pin "1") (pinfunction "1_1") (pintype "passive"))
      (node (ref "C17") (pin "1") (pinfunction "1_1") (pintype "passive"))
      (node (ref "C23") (pin "1") (pinfunction "1_1") (pintype "passive"))
      (node (ref "C24") (pin "1") (pinfunction "+_1") (pintype "passive"))
      (node (ref "C6") (pin "1") (pinfunction "1_1") (pintype "passive"))
      (node (ref "C7") (pin "1") (pinfunction "1_1") (pintype "passive"))
      (node (ref "D2") (pin "C") (pinfunction "K_C") (pintype "passive"))
      (node (ref "D_BATT1") (pin "C") (pinfunction "K_C") (pintype "passive"))
      (node (ref "IC1") (pin "3") (pinfunction "INPUT_3") (pintype "passive"))
      (node (ref "IC2") (pin "4") (pinfunction "VCC_4") (pintype "passive"))
      (node (ref "IC2") (pin "8") (pinfunction "CE_8") (pintype "passive"))
      (node (ref "L1") (pin "2") (pinfunction "2_2") (pintype "passive"))
      (node (ref "LED2") (pin "2") (pinfunction "A_2") (pintype "passive"))
      (node (ref "LED4") (pin "2") (pinfunction "A_2") (pintype "passive"))
      (node (ref "R1") (pin "2") (pinfunction "2_2") (pintype "passive"))
      (node (ref "R2") (pin "1") (pinfunction "1_1") (pintype "passive"))
      (node (ref "Remot1") (pin "2") (pinfunction "2_2") (pintype "passive"))
      (node (ref "U2") (pin "34") (pinfunction "VBAT_34") (pintype "power_in"))
      (node (ref "U2") (pin "35") (pinfunction "VBAT_35") (pintype "power_in"))
      (node (ref "cs1") (pin "2") (pinfunction "-_2") (pintype "passive"))
    )
    (net (code "2") (name "/3.3v") (class "Default")
      (node (ref "C1") (pin "2") (pinfunction "2_2") (pintype "passive"))
      (node (ref "C2") (pin "2") (pinfunction "2_2") (pintype "passive"))
      (node (ref "C25") (pin "1") (pinfunction "1_1") (pintype "passive"))
      (node (ref "C3") (pin "2") (pinfunction "2_2") (pintype "passive"))
      (node (ref "C4") (pin "2") (pinfunction "2_2") (pintype "passive"))
      (node (ref "C5") (pin "1") (pinfunction "1_1") (pintype "passive"))
      (node (ref "C8") (pin "1") (pinfunction "1_1") (pintype "passive"))
      (node (ref "IC1") (pin "2") (pinfunction "OUTPUT_2") (pintype "passive"))
      (node (ref "IC1") (pin "4") (pinfunction "VOUT_4") (pintype "passive"))
      (node (ref "IC3") (pin "8") (pinfunction "VCC_8") (pintype "passive"))
      (node (ref "R24") (pin "2") (pinfunction "2_2") (pintype "passive"))
      (node (ref "R34") (pin "2") (pinfunction "2_2") (pintype "passive"))
      (node (ref "R35") (pin "2") (pinfunction "2_2") (pintype "passive"))
      (node (ref "R36") (pin "2") (pinfunction "2_2") (pintype "passive"))
      (node (ref "R38") (pin "2") (pinfunction "2_2") (pintype "passive"))
      (node (ref "R41") (pin "2") (pinfunction "2_2") (pintype "passive"))
      (node (ref "U3") (pin "1") (pinfunction "VBAT_1") (pintype "bidirectional"))
      (node (ref "U3") (pin "24") (pinfunction "VDD_24") (pintype "power_in"))
      (node (ref "U3") (pin "36") (pinfunction "VDD_36") (pintype "power_in"))
      (node (ref "U3") (pin "48") (pinfunction "VDD_48") (pintype "power_in"))
      (node (ref "U3") (pin "9") (pinfunction "VDDA_9") (pintype "power_in"))
    )
    (net (code "3") (name "/12v") (class "Default")
      (node (ref "C10") (pin "1") (pinfunction "+_1") (pintype "passive"))
      (node (ref "C11") (pin "1") (pinfunction "+_1") (pintype "passive"))
      (node (ref "C12") (pin "2") (pinfunction "2_2") (pintype "passive"))
      (node (ref "C13") (pin "1") (pinfunction "1_1") (pintype "passive"))
      (node (ref "C9") (pin "1") (pinfunction "+_1") (pintype "passive"))
      (node (ref "D3") (pin "2") (pintype "passive"))
      (node (ref "D6") (pin "2") (pintype "passive"))
      (node (ref "K1") (pin "3") (pinfunction "T1_3") (pintype "passive"))
      (node (ref "K2") (pin "3") (pinfunction "T1_3") (pintype "passive"))
      (node (ref "P1") (pin "1") (pinfunction "1_1") (pintype "passive"))
      (node (ref "P3") (pin "1") (pinfunction "1_1") (pintype "passive"))
      (node (ref "PS1") (pin "4") (pinfunction "+VO_4") (pintype "passive"))
      (node (ref "Q3") (pin "2") (pinfunction "E_2") (pintype "passive"))
      (node (ref "R10") (pin "1") (pinfunction "1_1") (pintype "passive"))
      (node (ref "R19") (pin "1") (pinfunction "1_1") (pintype "passive"))
      (node (ref "R25") (pin "1") (pinfunction "1_1") (pintype "passive"))
      (node (ref "R3") (pin "2") (pinfunction "2_2") (pintype "passive"))
      (node (ref "U1") (pin "1") (pinfunction "VIN_1") (pintype "passive"))
    )
    (net (code "4") (name "/CLK") (class "Default")
      (node (ref "PROGRAM1") (pin "3") (pinfunction "3_3") (pintype "passive"))
      (node (ref "U3") (pin "37") (pinfunction "PA14_37") (pintype "bidirectional"))
    )
    (net (code "5") (name "/DIO") (class "Default")
      (node (ref "PROGRAM1") (pin "4") (pinfunction "4_4") (pintype "passive"))
      (node (ref "U3") (pin "34") (pinfunction "PA13_34") (pintype "bidirectional"))
    )
    (net (code "6") (name "/N") (class "Default")
      (node (ref "PS1") (pin "2") (pinfunction "AC_2_2") (pintype "passive"))
      (node (ref "T1") (pin "1") (pinfunction "1_1") (pintype "passive"))
      (node (ref "battery2") (pin "2") (pinfunction "2_2") (pintype "passive"))
      (node (ref "battery5") (pin "2") (pinfunction "2_2") (pintype "passive"))
      (node (ref "out1") (pin "2") (pinfunction "2_2") (pintype "passive"))
      (node (ref "out2") (pin "2") (pinfunction "2_2") (pintype "passive"))
    )
    (net (code "7") (name "/ON_Queqtel") (class "Default")
      (node (ref "R33") (pin "2") (pinfunction "2_2") (pintype "passive"))
      (node (ref "U3") (pin "29") (pinfunction "PA8_29") (pintype "bidirectional"))
    )
    (net (code "8") (name "/P") (class "Default")
      (node (ref "C16") (pin "2") (pinfunction "2_2") (pintype "passive"))
      (node (ref "C18") (pin "2") (pinfunction "2_2") (pintype "passive"))
      (node (ref "K1") (pin "1") (pinfunction "COM_1") (pintype "passive"))
      (node (ref "K2") (pin "1") (pinfunction "COM_1") (pintype "passive"))
      (node (ref "PS1") (pin "1") (pinfunction "AC_1_1") (pintype "passive"))
      (node (ref "T1") (pin "2") (pinfunction "2_2") (pintype "passive"))
    )
    (net (code "9") (name "/PB4") (class "Default")
      (node (ref "R28") (pin "1") (pinfunction "1_1") (pintype "passive"))
      (node (ref "U3") (pin "40") (pinfunction "PB4_40") (pintype "bidirectional"))
    )
    (net (code "10") (name "/PB12") (class "Default")
      (node (ref "R36") (pin "1") (pinfunction "1_1") (pintype "passive"))
      (node (ref "R39") (pin "1") (pinfunction "1_1") (pintype "passive"))
      (node (ref "U3") (pin "25") (pinfunction "PB12_25") (pintype "bidirectional"))
    )
    (net (code "11") (name "/PB13") (class "Default")
      (node (ref "R42") (pin "1") (pinfunction "1_1") (pintype "passive"))
      (node (ref "R43") (pin "1") (pinfunction "1_1") (pintype "passive"))
      (node (ref "U3") (pin "26") (pinfunction "PB13_26") (pintype "bidirectional"))
    )
    (net (code "12") (name "/PB14") (class "Default")
      (node (ref "R29") (pin "1") (pinfunction "1_1") (pintype "passive"))
      (node (ref "R45") (pin "2") (pinfunction "2_2") (pintype "passive"))
      (node (ref "U3") (pin "27") (pinfunction "PB14_27") (pintype "bidirectional"))
    )
    (net (code "13") (name "/PB15") (class "Default")
      (node (ref "R30") (pin "1") (pinfunction "1_1") (pintype "passive"))
      (node (ref "R44") (pin "2") (pinfunction "2_2") (pintype "passive"))
      (node (ref "U3") (pin "28") (pinfunction "PB15_28") (pintype "bidirectional"))
    )
    (net (code "14") (name "/PC13") (class "Default")
      (node (ref "R23") (pin "1") (pinfunction "1_1") (pintype "passive"))
      (node (ref "U3") (pin "2") (pinfunction "PC13-TAMPER-RTC_2") (pintype "bidirectional"))
    )
    (net (code "15") (name "/P_1") (class "Default")
      (node (ref "K1") (pin "4") (pinfunction "NO_4") (pintype "passive"))
      (node (ref "R11") (pin "2") (pintype "passive"))
      (node (ref "R6") (pin "1") (pinfunction "1_1") (pintype "passive"))
      (node (ref "R7") (pin "1") (pinfunction "1_1") (pintype "passive"))
      (node (ref "out1") (pin "1") (pinfunction "1_1") (pintype "passive"))
    )
    (net (code "16") (name "/P_2") (class "Default")
      (node (ref "K2") (pin "4") (pinfunction "NO_4") (pintype "passive"))
      (node (ref "R11") (pin "1") (pintype "passive"))
      (node (ref "R17") (pin "1") (pinfunction "1_1") (pintype "passive"))
      (node (ref "R8") (pin "1") (pinfunction "1_1") (pintype "passive"))
      (node (ref "out2") (pin "1") (pinfunction "1_1") (pintype "passive"))
    )
    (net (code "17") (name "/Pa2") (class "Default")
      (node (ref "P2") (pin "2") (pinfunction "2_2") (pintype "passive"))
      (node (ref "U3") (pin "12") (pinfunction "PA2_12") (pintype "bidirectional"))
    )
    (net (code "18") (name "/Pa3") (class "Default")
      (node (ref "P2") (pin "3") (pinfunction "3_3") (pintype "passive"))
      (node (ref "U3") (pin "13") (pinfunction "PA3_13") (pintype "bidirectional"))
    )
    (net (code "19") (name "/Pa11") (class "Default")
      (node (ref "R31") (pin "1") (pinfunction "1_1") (pintype "passive"))
      (node (ref "R37") (pin "2") (pinfunction "2_2") (pintype "passive"))
      (node (ref "U3") (pin "32") (pinfunction "PA11_32") (pintype "bidirectional"))
    )
    (net (code "20") (name "/Pa12") (class "Default")
      (node (ref "R18") (pin "2") (pinfunction "2_2") (pintype "passive"))
      (node (ref "R32") (pin "1") (pinfunction "1_1") (pintype "passive"))
      (node (ref "U3") (pin "33") (pinfunction "PA12_33") (pintype "bidirectional"))
    )
    (net (code "21") (name "/RI") (class "Default")
      (node (ref "R35") (pin "1") (pinfunction "1_1") (pintype "passive"))
      (node (ref "U2") (pin "7") (pinfunction "RI_7") (pintype "output"))
      (node (ref "U3") (pin "22") (pinfunction "PB11_22") (pintype "bidirectional"))
    )
    (net (code "22") (name "/RLY_1") (class "Default")
      (node (ref "R9") (pin "2") (pinfunction "2_2") (pintype "passive"))
      (node (ref "U3") (pin "15") (pinfunction "PA5_15") (pintype "bidirectional"))
    )
    (net (code "23") (name "/RLY_2") (class "Default")
      (node (ref "R20") (pin "2") (pinfunction "2_2") (pintype "passive"))
      (node (ref "U3") (pin "16") (pinfunction "PA6_16") (pintype "bidirectional"))
    )
    (net (code "24") (name "/RST") (class "Default")
      (node (ref "C22") (pin "2") (pinfunction "2_2") (pintype "passive"))
      (node (ref "R24") (pin "1") (pinfunction "1_1") (pintype "passive"))
      (node (ref "U3") (pin "7") (pinfunction "NRST_7") (pintype "input"))
    )
    (net (code "25") (name "/RX") (class "Default")
      (node (ref "U2") (pin "2") (pinfunction "RXD_2") (pintype "input"))
      (node (ref "U3") (pin "30") (pinfunction "PA9_30") (pintype "bidirectional"))
    )
    (net (code "26") (name "/SCL") (class "Default")
      (node (ref "IC3") (pin "6") (pinfunction "SCL_6") (pintype "passive"))
      (node (ref "R38") (pin "1") (pinfunction "1_1") (pintype "passive"))
      (node (ref "U3") (pin "42") (pinfunction "PB6_42") (pintype "bidirectional"))
    )
    (net (code "27") (name "/SDA") (class "Default")
      (node (ref "IC3") (pin "5") (pinfunction "SDA_5") (pintype "passive"))
      (node (ref "R41") (pin "1") (pinfunction "1_1") (pintype "passive"))
      (node (ref "U3") (pin "43") (pinfunction "PB7_43") (pintype "bidirectional"))
    )
    (net (code "28") (name "/SIM_CLK") (class "Default")
      (node (ref "J1") (pin "C3") (pinfunction "CLK_C3") (pintype "bidirectional"))
      (node (ref "U2") (pin "16") (pinfunction "SIM_CLK_16") (pintype "output"))
    )
    (net (code "29") (name "/SIM_IO") (class "Default")
      (node (ref "J1") (pin "C7") (pinfunction "I/O_C7") (pintype "bidirectional"))
      (node (ref "U2") (pin "15") (pinfunction "SIM_DATA_15") (pintype "bidirectional"))
    )
    (net (code "30") (name "/SIM_RST") (class "Default")
      (node (ref "J1") (pin "C2") (pinfunction "RST_C2") (pintype "input"))
      (node (ref "U2") (pin "17") (pinfunction "SIM_RST_17") (pintype "output"))
    )
    (net (code "31") (name "/TX") (class "Default")
      (node (ref "R40") (pin "2") (pinfunction "2_2") (pintype "passive"))
      (node (ref "U2") (pin "1") (pinfunction "TXD_1") (pintype "output"))
    )
    (net (code "32") (name "/V_SIM") (class "Default")
      (node (ref "C26") (pin "1") (pinfunction "+_1") (pintype "passive"))
      (node (ref "J1") (pin "C1") (pinfunction "VCC_C1") (pintype "power_in"))
      (node (ref "U2") (pin "18") (pinfunction "SIM_VDD_18") (pintype "power_in"))
    )
    (net (code "33") (name "/WC") (class "Default")
      (node (ref "IC3") (pin "7") (pinfunction "~{WC}_7") (pintype "passive"))
      (node (ref "R34") (pin "1") (pinfunction "1_1") (pintype "passive"))
      (node (ref "U3") (pin "41") (pinfunction "PB5_41") (pintype "bidirectional"))
    )
    (net (code "34") (name "/current") (class "Default")
      (node (ref "C21") (pin "2") (pinfunction "2_2") (pintype "passive"))
      (node (ref "R13") (pin "2") (pinfunction "2_2") (pintype "passive"))
      (node (ref "U3") (pin "11") (pinfunction "PA1_11") (pintype "bidirectional"))
    )
    (net (code "35") (name "/pa0") (class "Default")
      (node (ref "R3") (pin "1") (pinfunction "1_1") (pintype "passive"))
      (node (ref "R5") (pin "2") (pinfunction "2_2") (pintype "passive"))
      (node (ref "U3") (pin "10") (pinfunction "PA0_WKUP_10") (pintype "bidirectional"))
    )
    (net (code "36") (name "GND") (class "Default")
      (node (ref "2.2k") (pin "2") (pinfunction "2_2") (pintype "passive"))
      (node (ref "ANT1") (pin "2") (pinfunction "2_2") (pintype "passive"))
      (node (ref "C1") (pin "1") (pinfunction "1_1") (pintype "passive"))
      (node (ref "C10") (pin "2") (pinfunction "-_2") (pintype "passive"))
      (node (ref "C11") (pin "2") (pinfunction "-_2") (pintype "passive"))
      (node (ref "C12") (pin "1") (pinfunction "1_1") (pintype "passive"))
      (node (ref "C13") (pin "2") (pinfunction "2_2") (pintype "passive"))
      (node (ref "C14") (pin "1") (pinfunction "1_1") (pintype "passive"))
      (node (ref "C15") (pin "2") (pinfunction "2_2") (pintype "passive"))
      (node (ref "C17") (pin "2") (pinfunction "2_2") (pintype "passive"))
      (node (ref "C19") (pin "1") (pinfunction "1_1") (pintype "passive"))
      (node (ref "C2") (pin "1") (pinfunction "1_1") (pintype "passive"))
      (node (ref "C20") (pin "1") (pinfunction "1_1") (pintype "passive"))
      (node (ref "C21") (pin "1") (pinfunction "1_1") (pintype "passive"))
      (node (ref "C22") (pin "1") (pinfunction "1_1") (pintype "passive"))
      (node (ref "C23") (pin "2") (pinfunction "2_2") (pintype "passive"))
      (node (ref "C24") (pin "2") (pinfunction "-_2") (pintype "passive"))
      (node (ref "C25") (pin "2") (pinfunction "2_2") (pintype "passive"))
      (node (ref "C26") (pin "2") (pinfunction "-_2") (pintype "passive"))
      (node (ref "C27") (pin "1") (pinfunction "1_1") (pintype "passive"))
      (node (ref "C28") (pin "1") (pinfunction "1_1") (pintype "passive"))
      (node (ref "C3") (pin "1") (pinfunction "1_1") (pintype "passive"))
      (node (ref "C4") (pin "1") (pinfunction "1_1") (pintype "passive"))
      (node (ref "C5") (pin "2") (pinfunction "2_2") (pintype "passive"))
      (node (ref "C6") (pin "2") (pinfunction "2_2") (pintype "passive"))
      (node (ref "C7") (pin "2") (pinfunction "2_2") (pintype "passive"))
      (node (ref "C8") (pin "2") (pinfunction "2_2") (pintype "passive"))
      (node (ref "C9") (pin "2") (pinfunction "-_2") (pintype "passive"))
      (node (ref "D1") (pin "1") (pintype "passive"))
      (node (ref "D4") (pin "1") (pintype "passive"))
      (node (ref "D8") (pin "1") (pintype "passive"))
      (node (ref "IC1") (pin "1") (pinfunction "ADJ/GND_1") (pintype "passive"))
      (node (ref "IC2") (pin "1") (pinfunction "TEMP_1") (pintype "passive"))
      (node (ref "IC2") (pin "3") (pinfunction "GND_3") (pintype "passive"))
      (node (ref "IC2") (pin "9") (pinfunction "EAD_9") (pintype "passive"))
      (node (ref "IC3") (pin "1") (pinfunction "E0_1") (pintype "passive"))
      (node (ref "IC3") (pin "2") (pinfunction "E1_2") (pintype "passive"))
      (node (ref "IC3") (pin "3") (pinfunction "E2_3") (pintype "passive"))
      (node (ref "IC3") (pin "4") (pinfunction "VSS_4") (pintype "passive"))
      (node (ref "J1") (pin "C5") (pinfunction "GND_C5") (pintype "power_in"))
      (node (ref "LD1") (pin "2") (pinfunction "K_2") (pintype "passive"))
      (node (ref "LD2") (pin "2") (pinfunction "K_2") (pintype "passive"))
      (node (ref "LED5") (pin "1") (pinfunction "K_1") (pintype "passive"))
      (node (ref "Out3") (pin "1") (pinfunction "1_1") (pintype "passive"))
      (node (ref "P1") (pin "3") (pinfunction "3_3") (pintype "passive"))
      (node (ref "P2") (pin "1") (pinfunction "1_1") (pintype "passive"))
      (node (ref "P3") (pin "3") (pinfunction "3_3") (pintype "passive"))
      (node (ref "PROGRAM1") (pin "1") (pinfunction "1_1") (pintype "passive"))
      (node (ref "PS1") (pin "3") (pinfunction "-VO_3") (pintype "passive"))
      (node (ref "Q1") (pin "2") (pinfunction "E_2") (pintype "passive"))
      (node (ref "Q2") (pin "2") (pinfunction "E_2") (pintype "passive"))
      (node (ref "Q4") (pin "3") (pinfunction "S_3") (pintype "passive"))
      (node (ref "Q5") (pin "2") (pinfunction "E_2") (pintype "passive"))
      (node (ref "Q6") (pin "2") (pinfunction "E_2") (pintype "passive"))
      (node (ref "R14") (pin "2") (pinfunction "2_2") (pintype "passive"))
      (node (ref "R16") (pin "1") (pinfunction "1_1") (pintype "passive"))
      (node (ref "R22") (pin "2") (pinfunction "2_2") (pintype "passive"))
      (node (ref "R27") (pin "2") (pinfunction "2_2") (pintype "passive"))
      (node (ref "R29") (pin "2") (pinfunction "2_2") (pintype "passive"))
      (node (ref "R30") (pin "2") (pinfunction "2_2") (pintype "passive"))
      (node (ref "R31") (pin "2") (pinfunction "2_2") (pintype "passive"))
      (node (ref "R32") (pin "2") (pinfunction "2_2") (pintype "passive"))
      (node (ref "R4") (pin "1") (pinfunction "1_1") (pintype "passive"))
      (node (ref "R43") (pin "2") (pinfunction "2_2") (pintype "passive"))
      (node (ref "R5") (pin "1") (pinfunction "1_1") (pintype "passive"))
      (node (ref "Remot1") (pin "1") (pinfunction "1_1") (pintype "passive"))
      (node (ref "U1") (pin "3") (pinfunction "GND_3") (pintype "passive"))
      (node (ref "U1") (pin "5") (pinfunction "ON/OFF_5") (pintype "passive"))
      (node (ref "U2") (pin "13") (pinfunction "GND_13") (pintype "power_in"))
      (node (ref "U2") (pin "19") (pinfunction "GND_19") (pintype "power_in"))
      (node (ref "U2") (pin "21") (pinfunction "GND_21") (pintype "power_in"))
      (node (ref "U2") (pin "27") (pinfunction "GND_27") (pintype "power_in"))
      (node (ref "U2") (pin "30") (pinfunction "GND_30") (pintype "power_in"))
      (node (ref "U2") (pin "31") (pinfunction "GND_31") (pintype "power_in"))
      (node (ref "U2") (pin "33") (pinfunction "GND_33") (pintype "power_in"))
      (node (ref "U2") (pin "36") (pinfunction "GND_36") (pintype "power_in"))
      (node (ref "U2") (pin "37") (pinfunction "GND_37") (pintype "power_in"))
      (node (ref "U2") (pin "8") (pinfunction "GND_8") (pintype "power_in"))
      (node (ref "U3") (pin "23") (pinfunction "VSS_23") (pintype "power_in"))
      (node (ref "U3") (pin "35") (pinfunction "VSS_35") (pintype "power_in"))
      (node (ref "U3") (pin "44") (pinfunction "BOOT0_44") (pintype "input"))
      (node (ref "U3") (pin "47") (pinfunction "VSS_47") (pintype "power_in"))
      (node (ref "U3") (pin "8") (pinfunction "VSSA_8") (pintype "power_in"))
      (node (ref "battery1") (pin "1") (pinfunction "1_1") (pintype "passive"))
      (node (ref "battery3") (pin "2") (pinfunction "2_2") (pintype "passive"))
      (node (ref "battery4") (pin "1") (pinfunction "1_1") (pintype "passive"))
      (node (ref "cs1") (pin "1") (pinfunction "+_1") (pintype "passive"))
    )
    (net (code "37") (name "Net-(Buzzer1-Pad1)") (class "Default")
      (node (ref "Buzzer1") (pin "1") (pinfunction "1_1") (pintype "passive"))
      (node (ref "Out3") (pin "2") (pinfunction "2_2") (pintype "passive"))
      (node (ref "R25") (pin "2") (pinfunction "2_2") (pintype "passive"))
    )
    (net (code "38") (name "Net-(C16-Pad1)") (class "Default")
      (node (ref "C16") (pin "1") (pinfunction "1_1") (pintype "passive"))
      (node (ref "R6") (pin "2") (pinfunction "2_2") (pintype "passive"))
    )
    (net (code "39") (name "Net-(C18-Pad1)") (class "Default")
      (node (ref "C18") (pin "1") (pinfunction "1_1") (pintype "passive"))
      (node (ref "R17") (pin "2") (pinfunction "2_2") (pintype "passive"))
    )
    (net (code "40") (name "Net-(C19-Pad2)") (class "Default")
      (node (ref "C19") (pin "2") (pinfunction "2_2") (pintype "passive"))
      (node (ref "D5") (pin "2") (pintype "passive"))
      (node (ref "D7") (pin "2") (pintype "passive"))
      (node (ref "R12") (pin "1") (pinfunction "1_1") (pintype "passive"))
      (node (ref "R16") (pin "2") (pinfunction "2_2") (pintype "passive"))
    )
    (net (code "41") (name "Net-(C20-Pad2)") (class "Default")
      (node (ref "C20") (pin "2") (pinfunction "2_2") (pintype "passive"))
      (node (ref "R12") (pin "2") (pinfunction "2_2") (pintype "passive"))
      (node (ref "R13") (pin "1") (pinfunction "1_1") (pintype "passive"))
    )
    (net (code "42") (name "Net-(D4-Pad2)") (class "Default")
      (node (ref "D4") (pin "2") (pintype "passive"))
      (node (ref "D7") (pin "1") (pintype "passive"))
      (node (ref "T2") (pin "1") (pinfunction "1_1") (pintype "passive"))
    )
    (net (code "43") (name "Net-(D5-Pad1)") (class "Default")
      (node (ref "D5") (pin "1") (pintype "passive"))
      (node (ref "D8") (pin "2") (pintype "passive"))
      (node (ref "T2") (pin "2") (pinfunction "2_2") (pintype "passive"))
    )
    (net (code "44") (name "Net-(D_BATT1-PadA)") (class "Default")
      (node (ref "D_BATT1") (pin "A") (pinfunction "A_A") (pintype "passive"))
      (node (ref "PROGRAM1") (pin "2") (pinfunction "2_2") (pintype "passive"))
    )
    (net (code "45") (name "Net-(IC2-BAT)") (class "Default")
      (node (ref "D2") (pin "A") (pinfunction "A_A") (pintype "passive"))
      (node (ref "IC2") (pin "5") (pinfunction "BAT_5") (pintype "passive"))
      (node (ref "S1") (pin "1") (pinfunction "1_1") (pintype "passive"))
    )
    (net (code "46") (name "Net-(IC2-PROG)") (class "Default")
      (node (ref "2.2k") (pin "1") (pinfunction "1_1") (pintype "passive"))
      (node (ref "IC2") (pin "2") (pinfunction "PROG_2") (pintype "passive"))
    )
    (net (code "47") (name "Net-(IC2-~{CHRG})") (class "Default")
      (node (ref "IC2") (pin "7") (pinfunction "~{CHRG}_7") (pintype "passive"))
      (node (ref "R15") (pin "2") (pinfunction "2_2") (pintype "passive"))
    )
    (net (code "48") (name "Net-(IC2-~{STDBY})") (class "Default")
      (node (ref "IC2") (pin "6") (pinfunction "~{STDBY}_6") (pintype "passive"))
      (node (ref "R21") (pin "2") (pinfunction "2_2") (pintype "passive"))
    )
    (net (code "49") (name "Net-(K1-T2)") (class "Default")
      (node (ref "D3") (pin "1") (pintype "passive"))
      (node (ref "K1") (pin "2") (pinfunction "T2_2") (pintype "passive"))
      (node (ref "LED1") (pin "1") (pinfunction "K_1") (pintype "passive"))
      (node (ref "Q1") (pin "3") (pinfunction "C_3") (pintype "passive"))
      (node (ref "battery1") (pin "2") (pinfunction "2_2") (pintype "passive"))
    )
    (net (code "50") (name "Net-(K2-T2)") (class "Default")
      (node (ref "D6") (pin "1") (pintype "passive"))
      (node (ref "K2") (pin "2") (pinfunction "T2_2") (pintype "passive"))
      (node (ref "LED3") (pin "1") (pinfunction "K_1") (pintype "passive"))
      (node (ref "Q2") (pin "3") (pinfunction "C_3") (pintype "passive"))
      (node (ref "battery4") (pin "2") (pinfunction "2_2") (pintype "passive"))
    )
    (net (code "51") (name "Net-(LD1-A)") (class "Default")
      (node (ref "LD1") (pin "1") (pinfunction "A_1") (pintype "passive"))
      (node (ref "R2") (pin "2") (pinfunction "2_2") (pintype "passive"))
    )
    (net (code "52") (name "Net-(LD2-A)") (class "Default")
      (node (ref "LD2") (pin "1") (pinfunction "A_1") (pintype "passive"))
      (node (ref "R23") (pin "2") (pinfunction "2_2") (pintype "passive"))
    )
    (net (code "53") (name "Net-(LED1-A)") (class "Default")
      (node (ref "LED1") (pin "2") (pinfunction "A_2") (pintype "passive"))
      (node (ref "R10") (pin "2") (pinfunction "2_2") (pintype "passive"))
    )
    (net (code "54") (name "Net-(LED2-K)") (class "Default")
      (node (ref "LED2") (pin "1") (pinfunction "K_1") (pintype "passive"))
      (node (ref "R15") (pin "1") (pinfunction "1_1") (pintype "passive"))
    )
    (net (code "55") (name "Net-(LED3-A)") (class "Default")
      (node (ref "LED3") (pin "2") (pinfunction "A_2") (pintype "passive"))
      (node (ref "R19") (pin "2") (pinfunction "2_2") (pintype "passive"))
    )
    (net (code "56") (name "Net-(LED4-K)") (class "Default")
      (node (ref "LED4") (pin "1") (pinfunction "K_1") (pintype "passive"))
      (node (ref "R21") (pin "1") (pinfunction "1_1") (pintype "passive"))
    )
    (net (code "57") (name "Net-(LED5-A)") (class "Default")
      (node (ref "4.7k") (pin "2") (pinfunction "2_2") (pintype "passive"))
      (node (ref "LED5") (pin "2") (pinfunction "A_2") (pintype "passive"))
    )
    (net (code "58") (name "Net-(P1-Pad2)") (class "Default")
      (node (ref "P1") (pin "2") (pinfunction "2_2") (pintype "passive"))
      (node (ref "R39") (pin "2") (pinfunction "2_2") (pintype "passive"))
    )
    (net (code "59") (name "Net-(P3-Pad2)") (class "Default")
      (node (ref "P3") (pin "2") (pinfunction "2_2") (pintype "passive"))
      (node (ref "R42") (pin "2") (pinfunction "2_2") (pintype "passive"))
    )
    (net (code "60") (name "Net-(Q1-B)") (class "Default")
      (node (ref "Q1") (pin "1") (pinfunction "B_1") (pintype "passive"))
      (node (ref "R14") (pin "1") (pinfunction "1_1") (pintype "passive"))
      (node (ref "R9") (pin "1") (pinfunction "1_1") (pintype "passive"))
    )
    (net (code "61") (name "Net-(Q2-B)") (class "Default")
      (node (ref "Q2") (pin "1") (pinfunction "B_1") (pintype "passive"))
      (node (ref "R20") (pin "1") (pinfunction "1_1") (pintype "passive"))
      (node (ref "R22") (pin "1") (pinfunction "1_1") (pintype "passive"))
    )
    (net (code "62") (name "Net-(Q3-B)") (class "Default")
      (node (ref "Q3") (pin "1") (pinfunction "B_1") (pintype "passive"))
      (node (ref "R26") (pin "2") (pinfunction "2_2") (pintype "passive"))
    )
    (net (code "63") (name "Net-(Q3-C)") (class "Default")
      (node (ref "Q3") (pin "3") (pinfunction "C_3") (pintype "passive"))
      (node (ref "Q4") (pin "1") (pinfunction "G_1") (pintype "passive"))
      (node (ref "R27") (pin "1") (pinfunction "1_1") (pintype "passive"))
    )
    (net (code "64") (name "Net-(Q4-D)") (class "Default")
      (node (ref "Buzzer1") (pin "2") (pinfunction "2_2") (pintype "passive"))
      (node (ref "Q4") (pin "2") (pinfunction "D_2") (pintype "passive"))
    )
    (net (code "65") (name "Net-(Q5-B)") (class "Default")
      (node (ref "Q5") (pin "1") (pinfunction "B_1") (pintype "passive"))
      (node (ref "R28") (pin "2") (pinfunction "2_2") (pintype "passive"))
    )
    (net (code "66") (name "Net-(Q5-C)") (class "Default")
      (node (ref "Q5") (pin "3") (pinfunction "C_3") (pintype "passive"))
      (node (ref "R26") (pin "1") (pinfunction "1_1") (pintype "passive"))
    )
    (net (code "67") (name "Net-(Q6-B)") (class "Default")
      (node (ref "Q6") (pin "1") (pinfunction "B_1") (pintype "passive"))
      (node (ref "R33") (pin "1") (pinfunction "1_1") (pintype "passive"))
    )
    (net (code "68") (name "Net-(Q6-C)") (class "Default")
      (node (ref "Q6") (pin "3") (pinfunction "C_3") (pintype "passive"))
      (node (ref "U2") (pin "39") (pinfunction "PWRKEY_39") (pintype "input"))
    )
    (net (code "69") (name "Net-(R7-Pad2)") (class "Default")
      (node (ref "R7") (pin "2") (pinfunction "2_2") (pintype "passive"))
      (node (ref "battery2") (pin "1") (pinfunction "1_1") (pintype "passive"))
    )
    (net (code "70") (name "Net-(R8-Pad2)") (class "Default")
      (node (ref "R8") (pin "2") (pinfunction "2_2") (pintype "passive"))
      (node (ref "battery5") (pin "1") (pinfunction "1_1") (pintype "passive"))
    )
    (net (code "71") (name "Net-(R18-Pad1)") (class "Default")
      (node (ref "R18") (pin "1") (pinfunction "1_1") (pintype "passive"))
      (node (ref "Remot1") (pin "3") (pinfunction "3_3") (pintype "passive"))
    )
    (net (code "72") (name "Net-(R37-Pad1)") (class "Default")
      (node (ref "R37") (pin "1") (pinfunction "1_1") (pintype "passive"))
      (node (ref "Remot1") (pin "4") (pinfunction "4_4") (pintype "passive"))
    )
    (net (code "73") (name "Net-(R44-Pad1)") (class "Default")
      (node (ref "R44") (pin "1") (pinfunction "1_1") (pintype "passive"))
      (node (ref "Remot1") (pin "5") (pinfunction "5_5") (pintype "passive"))
    )
    (net (code "74") (name "Net-(R45-Pad1)") (class "Default")
      (node (ref "R45") (pin "1") (pinfunction "1_1") (pintype "passive"))
      (node (ref "Remot1") (pin "6") (pinfunction "6_6") (pintype "passive"))
    )
    (net (code "75") (name "Net-(S1-Pad2)") (class "Default")
      (node (ref "S1") (pin "2") (pinfunction "2_2") (pintype "passive"))
      (node (ref "battery3") (pin "1") (pinfunction "1_1") (pintype "passive"))
    )
    (net (code "76") (name "Net-(U1-FB)") (class "Default")
      (node (ref "R1") (pin "1") (pinfunction "1_1") (pintype "passive"))
      (node (ref "R4") (pin "2") (pinfunction "2_2") (pintype "passive"))
      (node (ref "U1") (pin "4") (pinfunction "FB_4") (pintype "passive"))
    )
    (net (code "77") (name "Net-(U1-OUT)") (class "Default")
      (node (ref "D1") (pin "2") (pintype "passive"))
      (node (ref "L1") (pin "1") (pinfunction "1_1") (pintype "passive"))
      (node (ref "U1") (pin "2") (pinfunction "OUT_2") (pintype "passive"))
    )
    (net (code "78") (name "Net-(U2-NETLIGHT)") (class "Default")
      (node (ref "4.7k") (pin "1") (pinfunction "1_1") (pintype "passive"))
      (node (ref "U2") (pin "41") (pinfunction "NETLIGHT_41") (pintype "output"))
    )
    (net (code "79") (name "Net-(U2-RF_ANT)") (class "Default")
      (node (ref "ANT1") (pin "1") (pinfunction "1_1") (pintype "passive"))
      (node (ref "U2") (pin "32") (pinfunction "RF_ANT_32") (pintype "bidirectional"))
    )
    (net (code "80") (name "Net-(U3-PA10)") (class "Default")
      (node (ref "R40") (pin "1") (pinfunction "1_1") (pintype "passive"))
      (node (ref "U3") (pin "31") (pinfunction "PA10_31") (pintype "bidirectional"))
    )
    (net (code "81") (name "Net-(U3-PD0_OSC_IN)") (class "Default")
      (node (ref "C27") (pin "2") (pinfunction "2_2") (pintype "passive"))
      (node (ref "U3") (pin "5") (pinfunction "PD0_OSC_IN_5") (pintype "bidirectional"))
      (node (ref "Y1") (pin "1") (pinfunction "1_1") (pintype "passive"))
    )
    (net (code "82") (name "Net-(U3-PD1_OSC_OUT)") (class "Default")
      (node (ref "C28") (pin "2") (pinfunction "2_2") (pintype "passive"))
      (node (ref "U3") (pin "6") (pinfunction "PD1_OSC_OUT_6") (pintype "bidirectional"))
      (node (ref "Y1") (pin "2") (pinfunction "2_2") (pintype "passive"))
    )
    (net (code "83") (name "unconnected-(J1-VPP-PadC6)") (class "Default")
      (node (ref "J1") (pin "C6") (pinfunction "VPP_C6") (pintype "power_in"))
    )
    (net (code "84") (name "unconnected-(J2-Pad1)") (class "Default")
      (node (ref "J2") (pin "1") (pinfunction "1_1") (pintype "passive"))
    )
    (net (code "85") (name "unconnected-(J3-Pad1)") (class "Default")
      (node (ref "J3") (pin "1") (pinfunction "1_1") (pintype "passive"))
    )
    (net (code "86") (name "unconnected-(J4-Pad1)") (class "Default")
      (node (ref "J4") (pin "1") (pinfunction "1_1") (pintype "passive"))
    )
    (net (code "87") (name "unconnected-(J5-Pad1)") (class "Default")
      (node (ref "J5") (pin "1") (pinfunction "1_1") (pintype "passive"))
    )
    (net (code "88") (name "unconnected-(J6-Pad1)") (class "Default")
      (node (ref "J6") (pin "1") (pinfunction "1_1") (pintype "passive"))
    )
    (net (code "89") (name "unconnected-(J7-Pad1)") (class "Default")
      (node (ref "J7") (pin "1") (pinfunction "1_1") (pintype "passive"))
    )
    (net (code "90") (name "unconnected-(K1-NC-Pad5)") (class "Default")
      (node (ref "K1") (pin "5") (pinfunction "NC_5") (pintype "passive"))
    )
    (net (code "91") (name "unconnected-(K2-NC-Pad5)") (class "Default")
      (node (ref "K2") (pin "5") (pinfunction "NC_5") (pintype "passive"))
    )
    (net (code "92") (name "unconnected-(Remot1-Pad7)") (class "Default")
      (node (ref "Remot1") (pin "7") (pinfunction "7_7") (pintype "passive"))
    )
    (net (code "93") (name "unconnected-(S1-Pad3)") (class "Default")
      (node (ref "S1") (pin "3") (pinfunction "3_3") (pintype "passive"))
    )
    (net (code "94") (name "unconnected-(U2-ADC-Pad38)") (class "Default")
      (node (ref "U2") (pin "38") (pinfunction "ADC_38") (pintype "input+no_connect"))
    )
    (net (code "95") (name "unconnected-(U2-CTS-Pad4)") (class "Default")
      (node (ref "U2") (pin "4") (pinfunction "CTS_4") (pintype "output"))
    )
    (net (code "96") (name "unconnected-(U2-DBG_RXD-Pad26)") (class "Default")
      (node (ref "U2") (pin "26") (pinfunction "DBG_RXD_26") (pintype "input+no_connect"))
    )
    (net (code "97") (name "unconnected-(U2-DBG_TXD-Pad25)") (class "Default")
      (node (ref "U2") (pin "25") (pinfunction "DBG_TXD_25") (pintype "output"))
    )
    (net (code "98") (name "unconnected-(U2-DCD-Pad5)") (class "Default")
      (node (ref "U2") (pin "5") (pinfunction "DCD_5") (pintype "output"))
    )
    (net (code "99") (name "unconnected-(U2-DTR-Pad6)") (class "Default")
      (node (ref "U2") (pin "6") (pinfunction "DTR_6") (pintype "input+no_connect"))
    )
    (net (code "100") (name "unconnected-(U2-MICN-Pad10)") (class "Default")
      (node (ref "U2") (pin "10") (pinfunction "MICN_10") (pintype "input+no_connect"))
    )
    (net (code "101") (name "unconnected-(U2-MICP-Pad9)") (class "Default")
      (node (ref "U2") (pin "9") (pinfunction "MICP_9") (pintype "input+no_connect"))
    )
    (net (code "102") (name "unconnected-(U2-NC-Pad20)") (class "Default")
      (node (ref "U2") (pin "20") (pinfunction "NC_20") (pintype "passive"))
    )
    (net (code "103") (name "unconnected-(U2-RESERVED-Pad24)") (class "Default")
      (node (ref "U2") (pin "24") (pinfunction "RESERVED_24") (pintype "passive"))
    )
    (net (code "104") (name "unconnected-(U2-RFTXMON-Pad29)") (class "Default")
      (node (ref "U2") (pin "29") (pinfunction "RFTXMON_29") (pintype "output"))
    )
    (net (code "105") (name "unconnected-(U2-RTS-Pad3)") (class "Default")
      (node (ref "U2") (pin "3") (pinfunction "RTS_3") (pintype "input+no_connect"))
    )
    (net (code "106") (name "unconnected-(U2-RXD_AUX-Pad23)") (class "Default")
      (node (ref "U2") (pin "23") (pinfunction "RXD_AUX_23") (pintype "input+no_connect"))
    )
    (net (code "107") (name "unconnected-(U2-SIM_PRESENCE-Pad14)") (class "Default")
      (node (ref "U2") (pin "14") (pinfunction "SIM_PRESENCE_14") (pintype "input+no_connect"))
    )
    (net (code "108") (name "unconnected-(U2-SPKN-Pad12)") (class "Default")
      (node (ref "U2") (pin "12") (pinfunction "SPKN_12") (pintype "output"))
    )
    (net (code "109") (name "unconnected-(U2-SPKP-Pad11)") (class "Default")
      (node (ref "U2") (pin "11") (pinfunction "SPKP_11") (pintype "output"))
    )
    (net (code "110") (name "unconnected-(U2-STATUS-Pad42)") (class "Default")
      (node (ref "U2") (pin "42") (pinfunction "STATUS_42") (pintype "output"))
    )
    (net (code "111") (name "unconnected-(U2-TXD_AUX-Pad22)") (class "Default")
      (node (ref "U2") (pin "22") (pinfunction "TXD_AUX_22") (pintype "output"))
    )
    (net (code "112") (name "unconnected-(U2-VDD_EXT-Pad40)") (class "Default")
      (node (ref "U2") (pin "40") (pinfunction "VDD_EXT_40") (pintype "power_in"))
    )
    (net (code "113") (name "unconnected-(U2-VRTC-Pad28)") (class "Default")
      (node (ref "U2") (pin "28") (pinfunction "VRTC_28") (pintype "power_in"))
    )
    (net (code "114") (name "unconnected-(U3-PA4-Pad14)") (class "Default")
      (node (ref "U3") (pin "14") (pinfunction "PA4_14") (pintype "bidirectional"))
    )
    (net (code "115") (name "unconnected-(U3-PA7-Pad17)") (class "Default")
      (node (ref "U3") (pin "17") (pinfunction "PA7_17") (pintype "bidirectional"))
    )
    (net (code "116") (name "unconnected-(U3-PA15-Pad38)") (class "Default")
      (node (ref "U3") (pin "38") (pinfunction "PA15_38") (pintype "bidirectional"))
    )
    (net (code "117") (name "unconnected-(U3-PB0-Pad18)") (class "Default")
      (node (ref "U3") (pin "18") (pinfunction "PB0_18") (pintype "bidirectional"))
    )
    (net (code "118") (name "unconnected-(U3-PB1-Pad19)") (class "Default")
      (node (ref "U3") (pin "19") (pinfunction "PB1_19") (pintype "bidirectional"))
    )
    (net (code "119") (name "unconnected-(U3-PB2-Pad20)") (class "Default")
      (node (ref "U3") (pin "20") (pinfunction "PB2_20") (pintype "bidirectional"))
    )
    (net (code "120") (name "unconnected-(U3-PB3-Pad39)") (class "Default")
      (node (ref "U3") (pin "39") (pinfunction "PB3_39") (pintype "bidirectional"))
    )
    (net (code "121") (name "unconnected-(U3-PB8-Pad45)") (class "Default")
      (node (ref "U3") (pin "45") (pinfunction "PB8_45") (pintype "bidirectional"))
    )
    (net (code "122") (name "unconnected-(U3-PB9-Pad46)") (class "Default")
      (node (ref "U3") (pin "46") (pinfunction "PB9_46") (pintype "bidirectional"))
    )
    (net (code "123") (name "unconnected-(U3-PB10-Pad21)") (class "Default")
      (node (ref "U3") (pin "21") (pinfunction "PB10_21") (pintype "bidirectional"))
    )
    (net (code "124") (name "unconnected-(U3-PC14-OSC32_IN-Pad3)") (class "Default")
      (node (ref "U3") (pin "3") (pinfunction "PC14-OSC32_IN_3") (pintype "bidirectional"))
    )
    (net (code "125") (name "unconnected-(U3-PC15-OSC32_OUT-Pad4)") (class "Default")
      (node (ref "U3") (pin "4") (pinfunction "PC15-OSC32_OUT_4") (pintype "bidirectional"))
    )
  )
)
